# H_Bridge_Mosate.net
KiCad netlist of a schematic drawn in Altium Designer
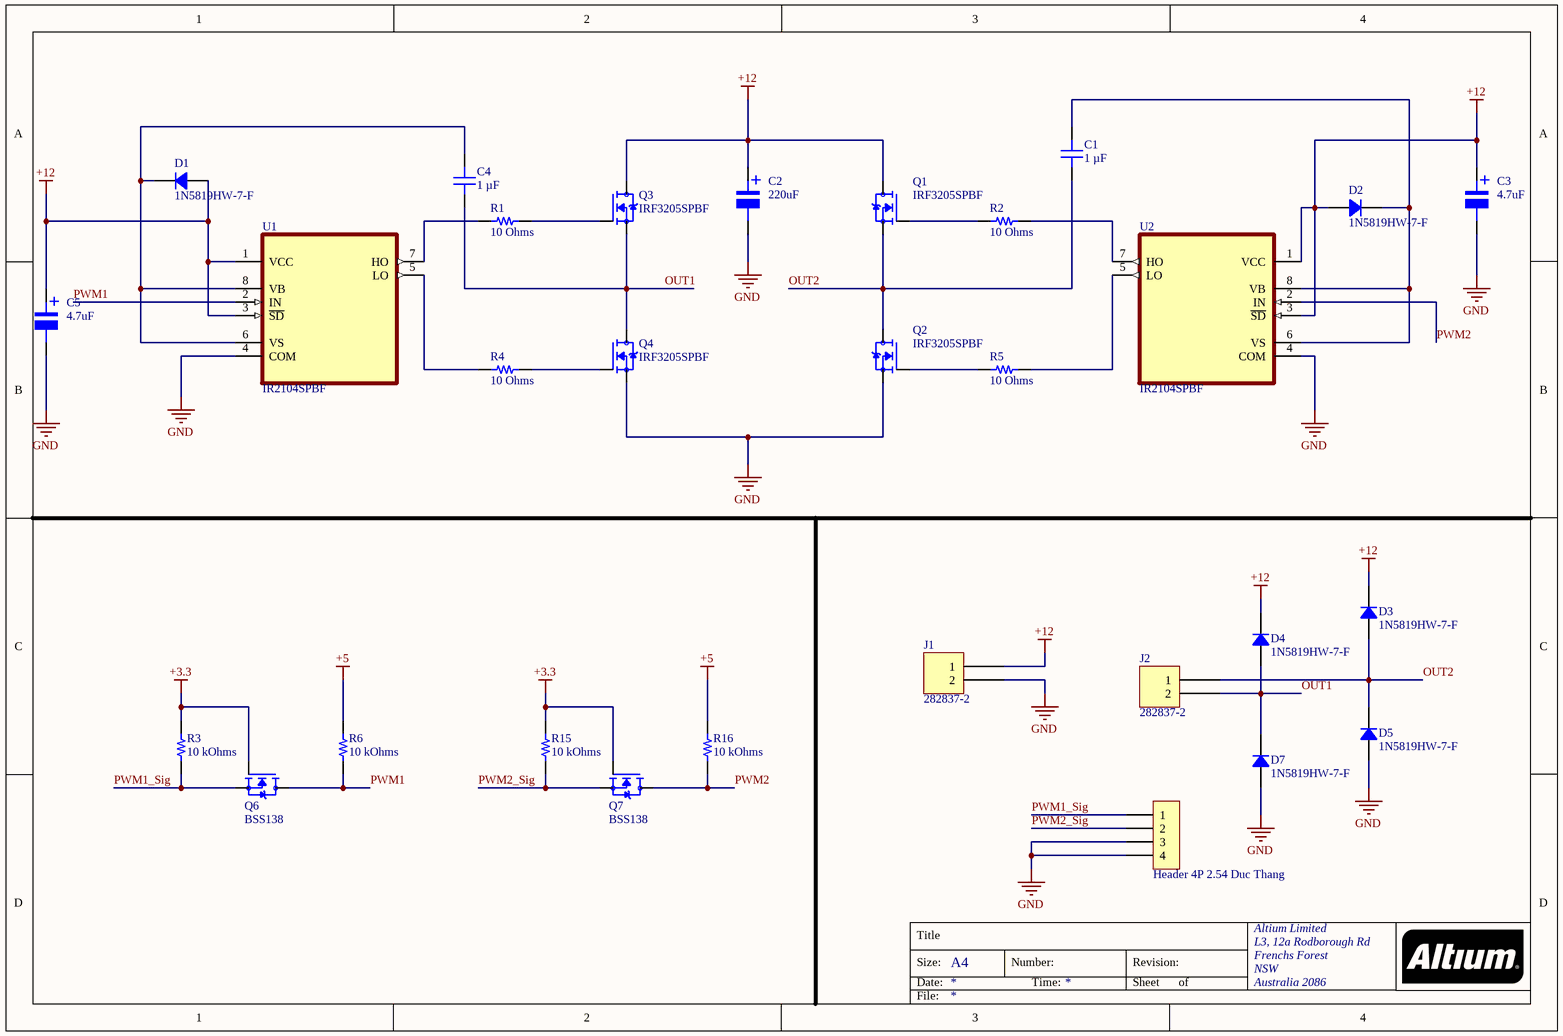
[diagram p0: H_Bridge_Mosate.SchDoc]

(export (version "E")
  (design (tool "Eeschema 10.0.6"))
  (components
    (comp (ref "C1")
      (value "1 µF")
      (footprint "CAP 0603_1608")
      (description "CAP CER 1UF 16V X8L 0603")
      (fields
        (field (name "PART NUMBER") "GCG188L8EE105KA07D")
        (field (name "MANUFACTURER") "Murata Electronics")
      )
      (libsource (lib "Celestial Altium Library - altium_library") (part "Capacitor"))
    )
    (comp (ref "C2")
      (value "220uF")
      (footprint "tu nhom 8 (f)")
      (description "Dán")
      (libsource (lib "Tu dien") (part "Tu Nhom 220uF 25V"))
    )
    (comp (ref "C3")
      (value "4.7uF")
      (footprint "tu nhom 4 (b)")
      (description "Dán")
      (libsource (lib "Tu dien") (part "Tu Nhom 4.7uF 25V"))
    )
    (comp (ref "C4")
      (value "1 µF")
      (footprint "CAP 0603_1608")
      (description "CAP CER 1UF 16V X8L 0603")
      (fields
        (field (name "PART NUMBER") "GCG188L8EE105KA07D")
        (field (name "MANUFACTURER") "Murata Electronics")
      )
      (libsource (lib "Celestial Altium Library - altium_library") (part "Capacitor"))
    )
    (comp (ref "C5")
      (value "4.7uF")
      (footprint "tu nhom 4 (b)")
      (description "Dán")
      (libsource (lib "Tu dien") (part "Tu Nhom 4.7uF 25V"))
    )
    (comp (ref "D1")
      (value "1N5819HW-7-F")
      (footprint "SOD-123")
      (description "DIODE SCHOTTKY 40V 1A SOD123")
      (fields (field (name "MANUFACTURER") "Diodes Incorporated"))
      (libsource (lib "Celestial Altium Library - altium_library") (part "Diode"))
    )
    (comp (ref "D2")
      (value "1N5819HW-7-F")
      (footprint "SOD-123")
      (description "DIODE SCHOTTKY 40V 1A SOD123")
      (fields (field (name "MANUFACTURER") "Diodes Incorporated"))
      (libsource (lib "Celestial Altium Library - altium_library") (part "Diode"))
    )
    (comp (ref "D3")
      (value "1N5819HW-7-F")
      (footprint "SOD-123")
      (description "DIODE SCHOTTKY 40V 1A SOD123")
      (fields (field (name "MANUFACTURER") "Diodes Incorporated"))
      (libsource (lib "Celestial Altium Library - altium_library") (part "Diode"))
    )
    (comp (ref "D4")
      (value "1N5819HW-7-F")
      (footprint "SOD-123")
      (description "DIODE SCHOTTKY 40V 1A SOD123")
      (fields (field (name "MANUFACTURER") "Diodes Incorporated"))
      (libsource (lib "Celestial Altium Library - altium_library") (part "Diode"))
    )
    (comp (ref "D5")
      (value "1N5819HW-7-F")
      (footprint "SOD-123")
      (description "DIODE SCHOTTKY 40V 1A SOD123")
      (fields (field (name "MANUFACTURER") "Diodes Incorporated"))
      (libsource (lib "Celestial Altium Library - altium_library") (part "Diode"))
    )
    (comp (ref "D7")
      (value "1N5819HW-7-F")
      (footprint "SOD-123")
      (description "DIODE SCHOTTKY 40V 1A SOD123")
      (fields (field (name "MANUFACTURER") "Diodes Incorporated"))
      (libsource (lib "Celestial Altium Library - altium_library") (part "Diode"))
    )
    (comp (ref "H1")
      (value "Header 4P 2.54 Duc Thang")
      (footprint "XH2.54M-4")
      (description "Cắm")
      (libsource (lib "Header") (part "Header 4P 2.54 Duc Thang"))
    )
    (comp (ref "J1")
      (value "282837-2")
      (footprint "TE 282837-2")
      (description "TERM BLK 2P SIDE ENT 5.08MM PCB")
      (fields (field (name "MANUFACTURER") "TE Connectivity AMP Connectors") (field (name "VOLTAGE") "300 V"))
      (libsource (lib "Celestial Altium Library - altium_library") (part "2 Pin"))
    )
    (comp (ref "J2")
      (value "282837-2")
      (footprint "TE 282837-2")
      (description "TERM BLK 2P SIDE ENT 5.08MM PCB")
      (fields (field (name "MANUFACTURER") "TE Connectivity AMP Connectors") (field (name "VOLTAGE") "300 V"))
      (libsource (lib "Celestial Altium Library - altium_library") (part "2 Pin"))
    )
    (comp (ref "Q1")
      (value "IRF3205SPBF")
      (footprint "TRANS_IRF3205SPBF")
      (fields (field (name "MF") "Infineon Technologies"))
      (libsource (lib "IRF3205SPBF") (part "IRF3205SPBF"))
    )
    (comp (ref "Q2")
      (value "IRF3205SPBF")
      (footprint "TRANS_IRF3205SPBF")
      (fields (field (name "MF") "Infineon Technologies"))
      (libsource (lib "IRF3205SPBF") (part "IRF3205SPBF"))
    )
    (comp (ref "Q3")
      (value "IRF3205SPBF")
      (footprint "TRANS_IRF3205SPBF")
      (fields (field (name "MF") "Infineon Technologies"))
      (libsource (lib "IRF3205SPBF") (part "IRF3205SPBF"))
    )
    (comp (ref "Q4")
      (value "IRF3205SPBF")
      (footprint "TRANS_IRF3205SPBF")
      (fields (field (name "MF") "Infineon Technologies"))
      (libsource (lib "IRF3205SPBF") (part "IRF3205SPBF"))
    )
    (comp (ref "Q6")
      (value "BSS138")
      (footprint "SOT95P240X111-3N")
      (description "N-Channel 50 V 220mA (Ta) 350mW (Ta) Surface Mount SOT-23-3")
      (fields (field (name "MF") "onsemi"))
      (libsource (lib "BSS138") (part "BSS138"))
    )
    (comp (ref "Q7")
      (value "BSS138")
      (footprint "SOT95P240X111-3N")
      (description "N-Channel 50 V 220mA (Ta) 350mW (Ta) Surface Mount SOT-23-3")
      (fields (field (name "MF") "onsemi"))
      (libsource (lib "BSS138") (part "BSS138"))
    )
    (comp (ref "R1")
      (value "10 Ohms")
      (footprint "RES 0603_1608")
      (description "RES 10 OHM 1% 1/4W 0603")
      (fields
        (field (name "PART NUMBER") "ERJ-UP3F10R0V")
        (field (name "MANUFACTURER") "Panasonic Electronic Components")
      )
      (libsource (lib "Celestial Altium Library - altium_library") (part "Resistor"))
    )
    (comp (ref "R2")
      (value "10 Ohms")
      (footprint "RES 0603_1608")
      (description "RES 10 OHM 1% 1/4W 0603")
      (fields
        (field (name "PART NUMBER") "ERJ-UP3F10R0V")
        (field (name "MANUFACTURER") "Panasonic Electronic Components")
      )
      (libsource (lib "Celestial Altium Library - altium_library") (part "Resistor"))
    )
    (comp (ref "R3")
      (value "10 kOhms")
      (footprint "RES 0603_1608")
      (description "RES SMD 10K OHM 1% 1/10W 0603")
      (fields (field (name "PART NUMBER") "AC0603FR-0710KL") (field (name "MANUFACTURER") "Yageo"))
      (libsource (lib "Celestial Altium Library - altium_library") (part "Resistor"))
    )
    (comp (ref "R4")
      (value "10 Ohms")
      (footprint "RES 0603_1608")
      (description "RES 10 OHM 1% 1/4W 0603")
      (fields
        (field (name "PART NUMBER") "ERJ-UP3F10R0V")
        (field (name "MANUFACTURER") "Panasonic Electronic Components")
      )
      (libsource (lib "Celestial Altium Library - altium_library") (part "Resistor"))
    )
    (comp (ref "R5")
      (value "10 Ohms")
      (footprint "RES 0603_1608")
      (description "RES 10 OHM 1% 1/4W 0603")
      (fields
        (field (name "PART NUMBER") "ERJ-UP3F10R0V")
        (field (name "MANUFACTURER") "Panasonic Electronic Components")
      )
      (libsource (lib "Celestial Altium Library - altium_library") (part "Resistor"))
    )
    (comp (ref "R6")
      (value "10 kOhms")
      (footprint "RES 0603_1608")
      (description "RES SMD 10K OHM 1% 1/10W 0603")
      (fields (field (name "PART NUMBER") "AC0603FR-0710KL") (field (name "MANUFACTURER") "Yageo"))
      (libsource (lib "Celestial Altium Library - altium_library") (part "Resistor"))
    )
    (comp (ref "R15")
      (value "10 kOhms")
      (footprint "RES 0603_1608")
      (description "RES SMD 10K OHM 1% 1/10W 0603")
      (fields (field (name "PART NUMBER") "AC0603FR-0710KL") (field (name "MANUFACTURER") "Yageo"))
      (libsource (lib "Celestial Altium Library - altium_library") (part "Resistor"))
    )
    (comp (ref "R16")
      (value "10 kOhms")
      (footprint "RES 0603_1608")
      (description "RES SMD 10K OHM 1% 1/10W 0603")
      (fields (field (name "PART NUMBER") "AC0603FR-0710KL") (field (name "MANUFACTURER") "Yageo"))
      (libsource (lib "Celestial Altium Library - altium_library") (part "Resistor"))
    )
    (comp (ref "U1")
      (value "IR2104SPBF")
      (footprint "SOIC127P600X175-8N")
      (fields (field (name "MF") "Infineon"))
      (libsource (lib "") (part "IR2104SPBF_1"))
    )
    (comp (ref "U2")
      (value "IR2104SPBF")
      (footprint "SOIC127P600X175-8N")
      (fields (field (name "MF") "Infineon"))
      (libsource (lib "IR2104SPBF") (part "IR2104SPBF"))
    )
  )
  (nets
    (net (code "1") (name "+3.3") (class "Default")
      (node (ref "Q6") (pin "1") (pinfunction "G_1") (pintype "passive"))
      (node (ref "Q7") (pin "1") (pinfunction "G_1") (pintype "passive"))
      (node (ref "R15") (pin "2") (pinfunction "2_2") (pintype "passive"))
      (node (ref "R3") (pin "2") (pinfunction "2_2") (pintype "passive"))
    )
    (net (code "2") (name "+5") (class "Default")
      (node (ref "R16") (pin "2") (pinfunction "2_2") (pintype "passive"))
      (node (ref "R6") (pin "2") (pinfunction "2_2") (pintype "passive"))
    )
    (net (code "3") (name "+12") (class "Default")
      (node (ref "C2") (pin "1") (pinfunction "1_1") (pintype "passive"))
      (node (ref "C3") (pin "1") (pinfunction "1_1") (pintype "passive"))
      (node (ref "C5") (pin "1") (pinfunction "1_1") (pintype "passive"))
      (node (ref "D1") (pin "1") (pinfunction "1_1") (pintype "passive"))
      (node (ref "D2") (pin "1") (pinfunction "1_1") (pintype "passive"))
      (node (ref "D3") (pin "2") (pinfunction "2_2") (pintype "passive"))
      (node (ref "D4") (pin "2") (pinfunction "2_2") (pintype "passive"))
      (node (ref "J1") (pin "1") (pinfunction "1_1") (pintype "passive"))
      (node (ref "Q1") (pin "2") (pinfunction "D_2") (pintype "passive"))
      (node (ref "Q3") (pin "2") (pinfunction "D_2") (pintype "passive"))
      (node (ref "U1") (pin "1") (pinfunction "VCC_1") (pintype "power_in"))
      (node (ref "U1") (pin "3") (pinfunction "~{SD}_3") (pintype "input"))
      (node (ref "U2") (pin "1") (pinfunction "VCC_1") (pintype "power_in"))
      (node (ref "U2") (pin "3") (pinfunction "~{SD}_3") (pintype "input"))
    )
    (net (code "4") (name "/OUT1") (class "Default")
      (node (ref "C4") (pin "1") (pinfunction "1_1") (pintype "passive"))
      (node (ref "D4") (pin "1") (pinfunction "1_1") (pintype "passive"))
      (node (ref "D7") (pin "2") (pinfunction "2_2") (pintype "passive"))
      (node (ref "J2") (pin "2") (pinfunction "2_2") (pintype "passive"))
      (node (ref "Q3") (pin "3") (pinfunction "S_3") (pintype "passive"))
      (node (ref "Q4") (pin "2") (pinfunction "D_2") (pintype "passive"))
    )
    (net (code "5") (name "/OUT2") (class "Default")
      (node (ref "C1") (pin "1") (pinfunction "1_1") (pintype "passive"))
      (node (ref "D3") (pin "1") (pinfunction "1_1") (pintype "passive"))
      (node (ref "D5") (pin "2") (pinfunction "2_2") (pintype "passive"))
      (node (ref "J2") (pin "1") (pinfunction "1_1") (pintype "passive"))
      (node (ref "Q1") (pin "3") (pinfunction "S_3") (pintype "passive"))
      (node (ref "Q2") (pin "2") (pinfunction "D_2") (pintype "passive"))
    )
    (net (code "6") (name "/PWM1") (class "Default")
      (node (ref "Q6") (pin "3") (pinfunction "D_3") (pintype "passive"))
      (node (ref "R6") (pin "1") (pinfunction "1_1") (pintype "passive"))
      (node (ref "U1") (pin "2") (pinfunction "IN_2") (pintype "input"))
    )
    (net (code "7") (name "/PWM1_Sig") (class "Default")
      (node (ref "H1") (pin "1") (pinfunction "1_1") (pintype "passive"))
      (node (ref "Q6") (pin "2") (pinfunction "S_2") (pintype "passive"))
      (node (ref "R3") (pin "1") (pinfunction "1_1") (pintype "passive"))
    )
    (net (code "8") (name "/PWM2") (class "Default")
      (node (ref "Q7") (pin "3") (pinfunction "D_3") (pintype "passive"))
      (node (ref "R16") (pin "1") (pinfunction "1_1") (pintype "passive"))
      (node (ref "U2") (pin "2") (pinfunction "IN_2") (pintype "input"))
    )
    (net (code "9") (name "/PWM2_Sig") (class "Default")
      (node (ref "H1") (pin "2") (pinfunction "2_2") (pintype "passive"))
      (node (ref "Q7") (pin "2") (pinfunction "S_2") (pintype "passive"))
      (node (ref "R15") (pin "1") (pinfunction "1_1") (pintype "passive"))
    )
    (net (code "10") (name "GND") (class "Default")
      (node (ref "C2") (pin "2") (pinfunction "2_2") (pintype "passive"))
      (node (ref "C3") (pin "2") (pinfunction "2_2") (pintype "passive"))
      (node (ref "C5") (pin "2") (pinfunction "2_2") (pintype "passive"))
      (node (ref "D5") (pin "1") (pinfunction "1_1") (pintype "passive"))
      (node (ref "D7") (pin "1") (pinfunction "1_1") (pintype "passive"))
      (node (ref "H1") (pin "3") (pinfunction "3_3") (pintype "passive"))
      (node (ref "H1") (pin "4") (pinfunction "4_4") (pintype "passive"))
      (node (ref "J1") (pin "2") (pinfunction "2_2") (pintype "passive"))
      (node (ref "Q2") (pin "3") (pinfunction "S_3") (pintype "passive"))
      (node (ref "Q4") (pin "3") (pinfunction "S_3") (pintype "passive"))
      (node (ref "U1") (pin "4") (pinfunction "COM_4") (pintype "passive"))
      (node (ref "U2") (pin "4") (pinfunction "COM_4") (pintype "passive"))
    )
    (net (code "11") (name "Net-(Q1-G)") (class "Default")
      (node (ref "Q1") (pin "1") (pinfunction "G_1") (pintype "passive"))
      (node (ref "R2") (pin "1") (pinfunction "1_1") (pintype "passive"))
    )
    (net (code "12") (name "Net-(Q2-G)") (class "Default")
      (node (ref "Q2") (pin "1") (pinfunction "G_1") (pintype "passive"))
      (node (ref "R5") (pin "1") (pinfunction "1_1") (pintype "passive"))
    )
    (net (code "13") (name "Net-(Q3-G)") (class "Default")
      (node (ref "Q3") (pin "1") (pinfunction "G_1") (pintype "passive"))
      (node (ref "R1") (pin "2") (pinfunction "2_2") (pintype "passive"))
    )
    (net (code "14") (name "Net-(Q4-G)") (class "Default")
      (node (ref "Q4") (pin "1") (pinfunction "G_1") (pintype "passive"))
      (node (ref "R4") (pin "2") (pinfunction "2_2") (pintype "passive"))
    )
    (net (code "15") (name "Net-(U1-HO)") (class "Default")
      (node (ref "R1") (pin "1") (pinfunction "1_1") (pintype "passive"))
      (node (ref "U1") (pin "7") (pinfunction "HO_7") (pintype "output"))
    )
    (net (code "16") (name "Net-(U1-LO)") (class "Default")
      (node (ref "R4") (pin "1") (pinfunction "1_1") (pintype "passive"))
      (node (ref "U1") (pin "5") (pinfunction "LO_5") (pintype "output"))
    )
    (net (code "17") (name "Net-(U1-VB)") (class "Default")
      (node (ref "C4") (pin "2") (pinfunction "2_2") (pintype "passive"))
      (node (ref "D1") (pin "2") (pinfunction "2_2") (pintype "passive"))
      (node (ref "U1") (pin "6") (pinfunction "VS_6") (pintype "power_in"))
      (node (ref "U1") (pin "8") (pinfunction "VB_8") (pintype "power_in"))
    )
    (net (code "18") (name "Net-(U2-HO)") (class "Default")
      (node (ref "R2") (pin "2") (pinfunction "2_2") (pintype "passive"))
      (node (ref "U2") (pin "7") (pinfunction "HO_7") (pintype "output"))
    )
    (net (code "19") (name "Net-(U2-LO)") (class "Default")
      (node (ref "R5") (pin "2") (pinfunction "2_2") (pintype "passive"))
      (node (ref "U2") (pin "5") (pinfunction "LO_5") (pintype "output"))
    )
    (net (code "20") (name "Net-(U2-VB)") (class "Default")
      (node (ref "C1") (pin "2") (pinfunction "2_2") (pintype "passive"))
      (node (ref "D2") (pin "2") (pinfunction "2_2") (pintype "passive"))
      (node (ref "U2") (pin "6") (pinfunction "VS_6") (pintype "power_in"))
      (node (ref "U2") (pin "8") (pinfunction "VB_8") (pintype "power_in"))
    )
  )
)
